# PCB2.net
KiCad netlist of a schematic drawn in EAGLE
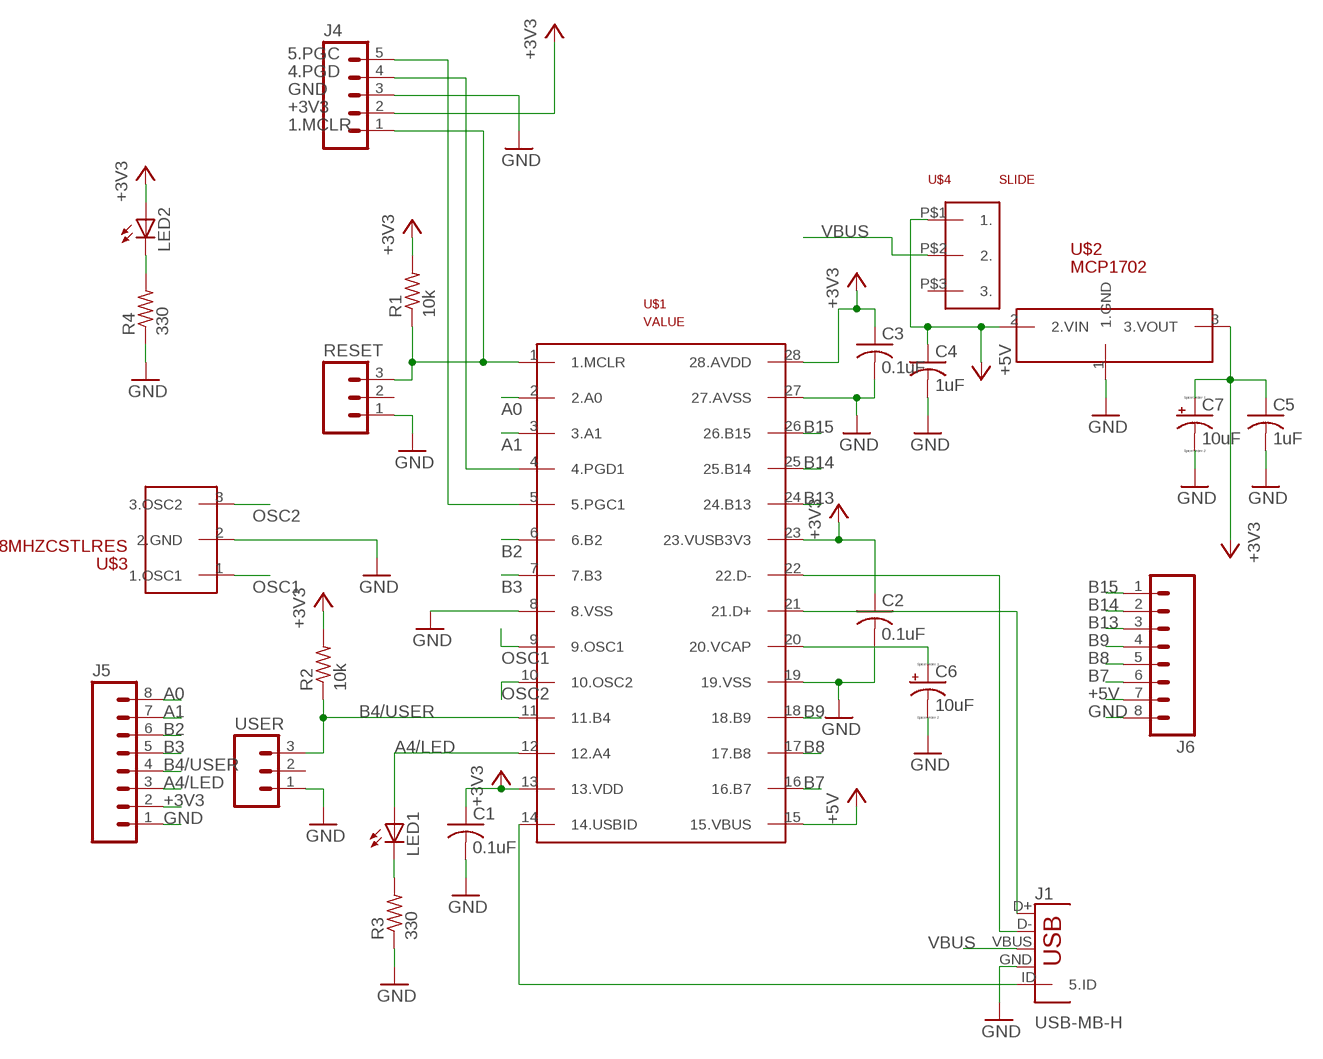
[diagram p0: schematic, sheet 1]

(export (version "E")
  (design (tool "Eeschema 10.0.6"))
  (components
    (comp (ref "C1")
      (value "0.1uF")
      (footprint "eagle-import:C025-024X044")
      (libsource (lib "eagle-import") (part "C-US025-024X044"))
    )
    (comp (ref "C2")
      (value "0.1uF")
      (footprint "eagle-import:C025-024X044")
      (libsource (lib "eagle-import") (part "C-US025-024X044"))
    )
    (comp (ref "C3")
      (value "0.1uF")
      (footprint "eagle-import:C025-024X044")
      (libsource (lib "eagle-import") (part "C-US025-024X044"))
    )
    (comp (ref "C4")
      (value "1uF")
      (footprint "eagle-import:C050-024X044")
      (libsource (lib "eagle-import") (part "C-US050-024X044"))
    )
    (comp (ref "C5")
      (value "1uF")
      (footprint "eagle-import:C050-024X044")
      (libsource (lib "eagle-import") (part "C-US050-024X044"))
    )
    (comp (ref "C6")
      (value "10uF")
      (footprint "eagle-import:TAP5-50")
      (libsource (lib "eagle-import") (part "CPOL-USTAP5-50"))
    )
    (comp (ref "C7")
      (value "10uF")
      (footprint "eagle-import:TAP5-50")
      (libsource (lib "eagle-import") (part "CPOL-USTAP5-50"))
    )
    (comp (ref "J1")
      (value "USB-MB-H")
      (footprint "eagle-import:USB-MB-H")
      (libsource (lib "eagle-import") (part "USB-MB-H"))
    )
    (comp (ref "J4")
      (value "M05PTH")
      (footprint "eagle-import:1X05")
      (libsource (lib "eagle-import") (part "M05PTH"))
    )
    (comp (ref "J5")
      (value "M08")
      (footprint "eagle-import:1X08_ROUND")
      (libsource (lib "eagle-import") (part "M08"))
    )
    (comp (ref "J6")
      (value "M08")
      (footprint "eagle-import:1X08_ROUND")
      (libsource (lib "eagle-import") (part "M08"))
    )
    (comp (ref "LED1")
      (value "LED3MM")
      (footprint "eagle-import:LED3MM")
      (libsource (lib "eagle-import") (part "LED3MM"))
    )
    (comp (ref "LED2")
      (value "LED3MM")
      (footprint "eagle-import:LED3MM")
      (libsource (lib "eagle-import") (part "LED3MM"))
    )
    (comp (ref "R1")
      (value "10k")
      (footprint "eagle-import:0207_10")
      (libsource (lib "eagle-import") (part "R-US_0207/10"))
    )
    (comp (ref "R2")
      (value "10k")
      (footprint "eagle-import:0207_10")
      (libsource (lib "eagle-import") (part "R-US_0207/10"))
    )
    (comp (ref "R3")
      (value "330")
      (footprint "eagle-import:0207_10")
      (libsource (lib "eagle-import") (part "R-US_0207/10"))
    )
    (comp (ref "R4")
      (value "330")
      (footprint "eagle-import:0207_10")
      (libsource (lib "eagle-import") (part "R-US_0207/10"))
    )
    (comp (ref "RESET")
      (value "M03PTH")
      (footprint "eagle-import:1X03")
      (libsource (lib "eagle-import") (part "M03PTH"))
    )
    (comp (ref "U$1")
      (value "PIC32MX250F128B")
      (footprint "eagle-import:DIL28-3")
      (libsource (lib "eagle-import") (part "PIC32MX250F128B"))
    )
    (comp (ref "U$2")
      (value "MCP1702")
      (footprint "eagle-import:TO92")
      (libsource (lib "eagle-import") (part "MCP1702"))
    )
    (comp (ref "U$3")
      (value "8MHZCSTLRES")
      (footprint "eagle-import:1X03")
      (libsource (lib "eagle-import") (part "8MHZCSTLRES"))
    )
    (comp (ref "U$4")
      (value "SLIDE")
      (footprint "eagle-import:SLIDE")
      (libsource (lib "eagle-import") (part "SLIDE"))
    )
    (comp (ref "USER")
      (value "M03PTH")
      (footprint "eagle-import:1X03")
      (libsource (lib "eagle-import") (part "M03PTH"))
    )
  )
  (nets
    (net (code "1") (name "+3V3") (class "Default")
      (node (ref "C1") (pin "1") (pinfunction "1_1") (pintype "passive"))
      (node (ref "C2") (pin "1") (pinfunction "1_1") (pintype "passive"))
      (node (ref "C3") (pin "1") (pinfunction "1_1") (pintype "passive"))
      (node (ref "C5") (pin "1") (pinfunction "1_1") (pintype "passive"))
      (node (ref "C7") (pin "+") (pinfunction "+_+") (pintype "passive"))
      (node (ref "J4") (pin "2") (pinfunction "2_2") (pintype "passive"))
      (node (ref "J5") (pin "2") (pinfunction "2_2") (pintype "passive"))
      (node (ref "LED2") (pin "A") (pinfunction "A_A") (pintype "passive"))
      (node (ref "R1") (pin "2") (pinfunction "2_2") (pintype "passive"))
      (node (ref "R2") (pin "2") (pinfunction "2_2") (pintype "passive"))
      (node (ref "U$1") (pin "13") (pinfunction "13.VDD_13") (pintype "bidirectional"))
      (node (ref "U$1") (pin "23") (pinfunction "23.VUSB3V3_23") (pintype "bidirectional"))
      (node (ref "U$1") (pin "28") (pinfunction "28.AVDD_28") (pintype "bidirectional"))
      (node (ref "U$2") (pin "3") (pinfunction "3.VOUT_3") (pintype "bidirectional"))
    )
    (net (code "2") (name "+5V") (class "Default")
      (node (ref "C4") (pin "1") (pinfunction "1_1") (pintype "passive"))
      (node (ref "J6") (pin "7") (pinfunction "7_7") (pintype "passive"))
      (node (ref "U$1") (pin "15") (pinfunction "15.VBUS_15") (pintype "bidirectional"))
      (node (ref "U$2") (pin "2") (pinfunction "2.VIN_2") (pintype "bidirectional"))
      (node (ref "U$4") (pin "P$1") (pinfunction "1._P$1") (pintype "bidirectional"))
    )
    (net (code "3") (name "/1.MCLR") (class "Default")
      (node (ref "J4") (pin "1") (pinfunction "1_1") (pintype "passive"))
      (node (ref "R1") (pin "1") (pinfunction "1_1") (pintype "passive"))
      (node (ref "RESET") (pin "3") (pinfunction "3_3") (pintype "passive"))
      (node (ref "U$1") (pin "1") (pinfunction "1.MCLR_1") (pintype "bidirectional"))
    )
    (net (code "4") (name "/4.PGD") (class "Default")
      (node (ref "J4") (pin "4") (pinfunction "4_4") (pintype "passive"))
      (node (ref "U$1") (pin "4") (pinfunction "4.PGD1_4") (pintype "bidirectional"))
    )
    (net (code "5") (name "/5.PGC") (class "Default")
      (node (ref "J4") (pin "5") (pinfunction "5_5") (pintype "passive"))
      (node (ref "U$1") (pin "5") (pinfunction "5.PGC1_5") (pintype "bidirectional"))
    )
    (net (code "6") (name "/A0") (class "Default")
      (node (ref "J5") (pin "8") (pinfunction "8_8") (pintype "passive"))
      (node (ref "U$1") (pin "2") (pinfunction "2.A0_2") (pintype "bidirectional"))
    )
    (net (code "7") (name "/A1") (class "Default")
      (node (ref "J5") (pin "7") (pinfunction "7_7") (pintype "passive"))
      (node (ref "U$1") (pin "3") (pinfunction "3.A1_3") (pintype "bidirectional"))
    )
    (net (code "8") (name "/A4{slash}LED") (class "Default")
      (node (ref "J5") (pin "3") (pinfunction "3_3") (pintype "passive"))
      (node (ref "LED1") (pin "A") (pinfunction "A_A") (pintype "passive"))
      (node (ref "U$1") (pin "12") (pinfunction "12.A4_12") (pintype "bidirectional"))
    )
    (net (code "9") (name "/B2") (class "Default")
      (node (ref "J5") (pin "6") (pinfunction "6_6") (pintype "passive"))
      (node (ref "U$1") (pin "6") (pinfunction "6.B2_6") (pintype "bidirectional"))
    )
    (net (code "10") (name "/B3") (class "Default")
      (node (ref "J5") (pin "5") (pinfunction "5_5") (pintype "passive"))
      (node (ref "U$1") (pin "7") (pinfunction "7.B3_7") (pintype "bidirectional"))
    )
    (net (code "11") (name "/B4{slash}USER") (class "Default")
      (node (ref "J5") (pin "4") (pinfunction "4_4") (pintype "passive"))
      (node (ref "R2") (pin "1") (pinfunction "1_1") (pintype "passive"))
      (node (ref "U$1") (pin "11") (pinfunction "11.B4_11") (pintype "bidirectional"))
      (node (ref "USER") (pin "3") (pinfunction "3_3") (pintype "passive"))
    )
    (net (code "12") (name "/B7") (class "Default")
      (node (ref "J6") (pin "6") (pinfunction "6_6") (pintype "passive"))
      (node (ref "U$1") (pin "16") (pinfunction "16.B7_16") (pintype "bidirectional"))
    )
    (net (code "13") (name "/B8") (class "Default")
      (node (ref "J6") (pin "5") (pinfunction "5_5") (pintype "passive"))
      (node (ref "U$1") (pin "17") (pinfunction "17.B8_17") (pintype "bidirectional"))
    )
    (net (code "14") (name "/B9") (class "Default")
      (node (ref "J6") (pin "4") (pinfunction "4_4") (pintype "passive"))
      (node (ref "U$1") (pin "18") (pinfunction "18.B9_18") (pintype "bidirectional"))
    )
    (net (code "15") (name "/B13") (class "Default")
      (node (ref "J6") (pin "3") (pinfunction "3_3") (pintype "passive"))
      (node (ref "U$1") (pin "24") (pinfunction "24.B13_24") (pintype "bidirectional"))
    )
    (net (code "16") (name "/B14") (class "Default")
      (node (ref "J6") (pin "2") (pinfunction "2_2") (pintype "passive"))
      (node (ref "U$1") (pin "25") (pinfunction "25.B14_25") (pintype "bidirectional"))
    )
    (net (code "17") (name "/B15") (class "Default")
      (node (ref "J6") (pin "1") (pinfunction "1_1") (pintype "passive"))
      (node (ref "U$1") (pin "26") (pinfunction "26.B15_26") (pintype "bidirectional"))
    )
    (net (code "18") (name "/OSC1") (class "Default")
      (node (ref "U$1") (pin "9") (pinfunction "9.OSC1_9") (pintype "bidirectional"))
      (node (ref "U$3") (pin "1") (pinfunction "1.OSC1_1") (pintype "bidirectional"))
    )
    (net (code "19") (name "/OSC2") (class "Default")
      (node (ref "U$1") (pin "10") (pinfunction "10.OSC2_10") (pintype "bidirectional"))
      (node (ref "U$3") (pin "3") (pinfunction "3.OSC2_3") (pintype "bidirectional"))
    )
    (net (code "20") (name "/VBUS") (class "Default")
      (node (ref "J1") (pin "VBUS") (pinfunction "VBUS_VBUS") (pintype "bidirectional"))
      (node (ref "U$4") (pin "P$2") (pinfunction "2._P$2") (pintype "bidirectional"))
    )
    (net (code "21") (name "GND") (class "Default")
      (node (ref "C1") (pin "2") (pinfunction "2_2") (pintype "passive"))
      (node (ref "C2") (pin "2") (pinfunction "2_2") (pintype "passive"))
      (node (ref "C3") (pin "2") (pinfunction "2_2") (pintype "passive"))
      (node (ref "C4") (pin "2") (pinfunction "2_2") (pintype "passive"))
      (node (ref "C5") (pin "2") (pinfunction "2_2") (pintype "passive"))
      (node (ref "C6") (pin "-") (pinfunction "-_-") (pintype "passive"))
      (node (ref "C7") (pin "-") (pinfunction "-_-") (pintype "passive"))
      (node (ref "J1") (pin "GND") (pinfunction "GND_GND") (pintype "bidirectional"))
      (node (ref "J4") (pin "3") (pinfunction "3_3") (pintype "passive"))
      (node (ref "J5") (pin "1") (pinfunction "1_1") (pintype "passive"))
      (node (ref "J6") (pin "8") (pinfunction "8_8") (pintype "passive"))
      (node (ref "R3") (pin "1") (pinfunction "1_1") (pintype "passive"))
      (node (ref "R4") (pin "1") (pinfunction "1_1") (pintype "passive"))
      (node (ref "RESET") (pin "1") (pinfunction "1_1") (pintype "passive"))
      (node (ref "U$1") (pin "19") (pinfunction "19.VSS_19") (pintype "bidirectional"))
      (node (ref "U$1") (pin "27") (pinfunction "27.AVSS_27") (pintype "bidirectional"))
      (node (ref "U$1") (pin "8") (pinfunction "8.VSS_8") (pintype "bidirectional"))
      (node (ref "U$2") (pin "1") (pinfunction "1.GND_1") (pintype "bidirectional"))
      (node (ref "U$3") (pin "2") (pinfunction "2.GND_2") (pintype "bidirectional"))
      (node (ref "USER") (pin "1") (pinfunction "1_1") (pintype "passive"))
    )
    (net (code "22") (name "Net-(J1-5.ID)") (class "Default")
      (node (ref "J1") (pin "ID") (pinfunction "5.ID_ID") (pintype "bidirectional"))
      (node (ref "U$1") (pin "14") (pinfunction "14.USBID_14") (pintype "bidirectional"))
    )
    (net (code "23") (name "Net-(LED1-C)") (class "Default")
      (node (ref "LED1") (pin "K") (pinfunction "C_K") (pintype "passive"))
      (node (ref "R3") (pin "2") (pinfunction "2_2") (pintype "passive"))
    )
    (net (code "24") (name "Net-(LED2-C)") (class "Default")
      (node (ref "LED2") (pin "K") (pinfunction "C_K") (pintype "passive"))
      (node (ref "R4") (pin "2") (pinfunction "2_2") (pintype "passive"))
    )
    (net (code "25") (name "Net-(U$1-20.VCAP)") (class "Default")
      (node (ref "C6") (pin "+") (pinfunction "+_+") (pintype "passive"))
      (node (ref "U$1") (pin "20") (pinfunction "20.VCAP_20") (pintype "bidirectional"))
    )
    (net (code "26") (name "Net-(U$1-21.D+)") (class "Default")
      (node (ref "J1") (pin "D+") (pinfunction "D+_D+") (pintype "bidirectional"))
      (node (ref "U$1") (pin "21") (pinfunction "21.D+_21") (pintype "bidirectional"))
    )
    (net (code "27") (name "Net-(U$1-22.D-)") (class "Default")
      (node (ref "J1") (pin "D-") (pinfunction "D-_D-") (pintype "bidirectional"))
      (node (ref "U$1") (pin "22") (pinfunction "22.D-_22") (pintype "bidirectional"))
    )
    (net (code "28") (name "unconnected-(RESET-Pad2)") (class "Default")
      (node (ref "RESET") (pin "2") (pinfunction "2_2") (pintype "passive"))
    )
    (net (code "29") (name "unconnected-(U$4-3.-PadP$3)") (class "Default")
      (node (ref "U$4") (pin "P$3") (pinfunction "3._P$3") (pintype "bidirectional"))
    )
    (net (code "30") (name "unconnected-(USER-Pad2)") (class "Default")
      (node (ref "USER") (pin "2") (pinfunction "2_2") (pintype "passive"))
    )
  )
)
